# Low_jitter_CLK_bypass.net
KiCad netlist of a schematic drawn in Altium Designer
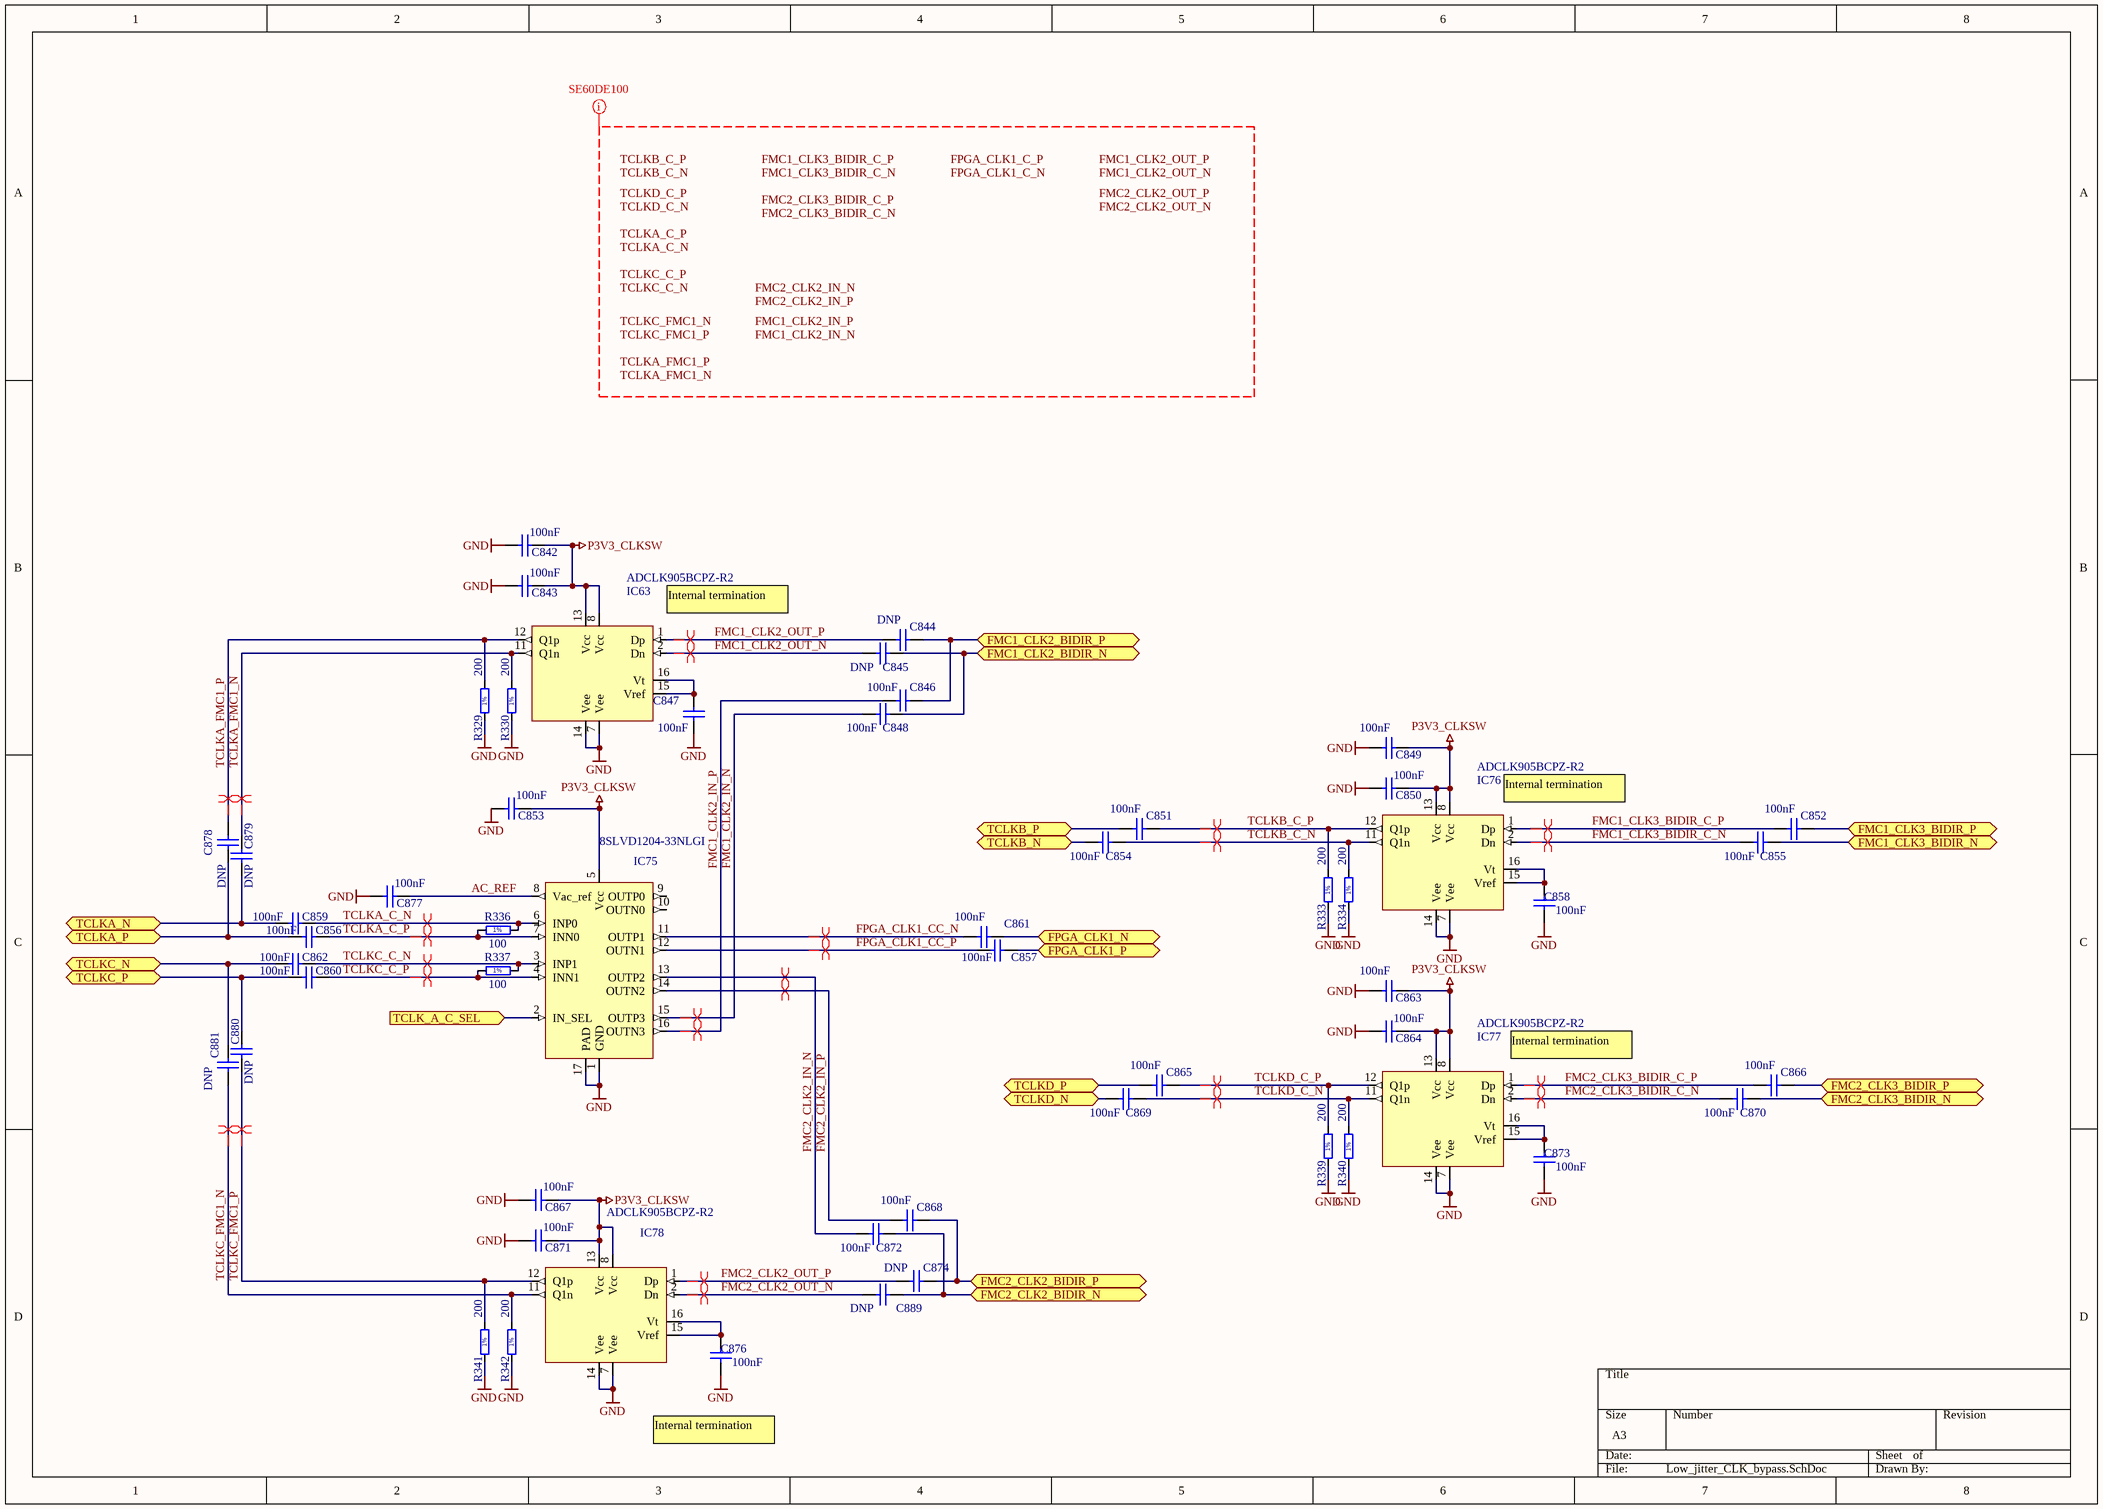
[diagram p0: Low_jitter_CLK_bypass.SchDoc]

(export (version "E")
  (design (tool "Eeschema 10.0.6"))
  (components
    (comp (ref "C842")
      (value "100nF")
      (footprint "CAPC0603X33N")
      (description "Non-polarised capacitor")
      (fields
        (field (name "PART NUMBER") "CC0201_100NF_6.3V_10%_X5R")
        (field (name "VOLTAGE") "6.3V")
        (field (name "AUTHOR") "CERN DEM JLC")
      )
      (libsource (lib "Capacitors") (part "Capacitor - non polarized"))
    )
    (comp (ref "C843")
      (value "100nF")
      (footprint "CAPC0603X33N")
      (description "Non-polarised capacitor")
      (fields
        (field (name "PART NUMBER") "CC0201_100NF_6.3V_10%_X5R")
        (field (name "VOLTAGE") "6.3V")
        (field (name "AUTHOR") "CERN DEM JLC")
      )
      (libsource (lib "Capacitors") (part "Capacitor - non polarized"))
    )
    (comp (ref "C844")
      (value "DNP")
      (footprint "CAPC0603X33N")
      (description "Non-polarised capacitor")
      (fields
        (field (name "PART NUMBER") "CC0201_100NF_6.3V_10%_X5R")
        (field (name "VOLTAGE") "6.3V")
        (field (name "AUTHOR") "CERN DEM JLC")
      )
      (libsource (lib "Capacitors") (part "Capacitor - non polarized"))
    )
    (comp (ref "C845")
      (value "DNP")
      (footprint "CAPC0603X33N")
      (description "Non-polarised capacitor")
      (fields
        (field (name "PART NUMBER") "CC0201_100NF_6.3V_10%_X5R")
        (field (name "VOLTAGE") "6.3V")
        (field (name "AUTHOR") "CERN DEM JLC")
      )
      (libsource (lib "Capacitors") (part "Capacitor - non polarized"))
    )
    (comp (ref "C846")
      (value "100nF")
      (footprint "CAPC0603X33N")
      (description "Non-polarised capacitor")
      (fields
        (field (name "PART NUMBER") "CC0201_100NF_6.3V_10%_X5R")
        (field (name "VOLTAGE") "6.3V")
        (field (name "AUTHOR") "CERN DEM JLC")
      )
      (libsource (lib "Capacitors") (part "Capacitor - non polarized"))
    )
    (comp (ref "C847")
      (value "100nF")
      (footprint "CAPC0603X33N")
      (description "Non-polarised capacitor")
      (fields
        (field (name "PART NUMBER") "CC0201_100NF_6.3V_10%_X5R")
        (field (name "VOLTAGE") "6.3V")
        (field (name "AUTHOR") "CERN DEM JLC")
      )
      (libsource (lib "Capacitors") (part "Capacitor - non polarized"))
    )
    (comp (ref "C848")
      (value "100nF")
      (footprint "CAPC0603X33N")
      (description "Non-polarised capacitor")
      (fields
        (field (name "PART NUMBER") "CC0201_100NF_6.3V_10%_X5R")
        (field (name "VOLTAGE") "6.3V")
        (field (name "AUTHOR") "CERN DEM JLC")
      )
      (libsource (lib "Capacitors") (part "Capacitor - non polarized"))
    )
    (comp (ref "C849")
      (value "100nF")
      (footprint "CAPC0603X33N")
      (description "Non-polarised capacitor")
      (fields
        (field (name "PART NUMBER") "CC0201_100NF_6.3V_10%_X5R")
        (field (name "VOLTAGE") "6.3V")
        (field (name "AUTHOR") "CERN DEM JLC")
      )
      (libsource (lib "Capacitors") (part "Capacitor - non polarized"))
    )
    (comp (ref "C850")
      (value "100nF")
      (footprint "CAPC0603X33N")
      (description "Non-polarised capacitor")
      (fields
        (field (name "PART NUMBER") "CC0201_100NF_6.3V_10%_X5R")
        (field (name "VOLTAGE") "6.3V")
        (field (name "AUTHOR") "CERN DEM JLC")
      )
      (libsource (lib "Capacitors") (part "Capacitor - non polarized"))
    )
    (comp (ref "C851")
      (value "100nF")
      (footprint "CAPC0603X33N")
      (description "Non-polarised capacitor")
      (fields
        (field (name "PART NUMBER") "CC0201_100NF_6.3V_10%_X5R")
        (field (name "VOLTAGE") "6.3V")
        (field (name "AUTHOR") "CERN DEM JLC")
      )
      (libsource (lib "Capacitors") (part "Capacitor - non polarized"))
    )
    (comp (ref "C852")
      (value "100nF")
      (footprint "CAPC0603X33N")
      (description "Non-polarised capacitor")
      (fields
        (field (name "PART NUMBER") "CC0201_100NF_6.3V_10%_X5R")
        (field (name "VOLTAGE") "6.3V")
        (field (name "AUTHOR") "CERN DEM JLC")
      )
      (libsource (lib "Capacitors") (part "Capacitor - non polarized"))
    )
    (comp (ref "C853")
      (value "100nF")
      (footprint "CAPC0603X33N")
      (description "Non-polarised capacitor")
      (fields
        (field (name "PART NUMBER") "CC0201_100NF_6.3V_10%_X5R")
        (field (name "VOLTAGE") "6.3V")
        (field (name "AUTHOR") "CERN DEM JLC")
      )
      (libsource (lib "Capacitors") (part "Capacitor - non polarized"))
    )
    (comp (ref "C854")
      (value "100nF")
      (footprint "CAPC0603X33N")
      (description "Non-polarised capacitor")
      (fields
        (field (name "PART NUMBER") "CC0201_100NF_6.3V_10%_X5R")
        (field (name "VOLTAGE") "6.3V")
        (field (name "AUTHOR") "CERN DEM JLC")
      )
      (libsource (lib "Capacitors") (part "Capacitor - non polarized"))
    )
    (comp (ref "C855")
      (value "100nF")
      (footprint "CAPC0603X33N")
      (description "Non-polarised capacitor")
      (fields
        (field (name "PART NUMBER") "CC0201_100NF_6.3V_10%_X5R")
        (field (name "VOLTAGE") "6.3V")
        (field (name "AUTHOR") "CERN DEM JLC")
      )
      (libsource (lib "Capacitors") (part "Capacitor - non polarized"))
    )
    (comp (ref "C856")
      (value "100nF")
      (footprint "CAPC0603X33N")
      (description "Non-polarised capacitor")
      (fields
        (field (name "PART NUMBER") "CC0201_100NF_6.3V_10%_X5R")
        (field (name "VOLTAGE") "6.3V")
        (field (name "AUTHOR") "CERN DEM JLC")
      )
      (libsource (lib "Capacitors") (part "Capacitor - non polarized"))
    )
    (comp (ref "C857")
      (value "100nF")
      (footprint "CAPC0603X33N")
      (description "Non-polarised capacitor")
      (fields
        (field (name "PART NUMBER") "CC0201_100NF_6.3V_10%_X5R")
        (field (name "VOLTAGE") "6.3V")
        (field (name "AUTHOR") "CERN DEM JLC")
      )
      (libsource (lib "Capacitors") (part "Capacitor - non polarized"))
    )
    (comp (ref "C858")
      (value "100nF")
      (footprint "CAPC0603X33N")
      (description "Non-polarised capacitor")
      (fields
        (field (name "PART NUMBER") "CC0201_100NF_6.3V_10%_X5R")
        (field (name "VOLTAGE") "6.3V")
        (field (name "AUTHOR") "CERN DEM JLC")
      )
      (libsource (lib "Capacitors") (part "Capacitor - non polarized"))
    )
    (comp (ref "C859")
      (value "100nF")
      (footprint "CAPC0603X33N")
      (description "Non-polarised capacitor")
      (fields
        (field (name "PART NUMBER") "CC0201_100NF_6.3V_10%_X5R")
        (field (name "VOLTAGE") "6.3V")
        (field (name "AUTHOR") "CERN DEM JLC")
      )
      (libsource (lib "Capacitors") (part "Capacitor - non polarized"))
    )
    (comp (ref "C860")
      (value "100nF")
      (footprint "CAPC0603X33N")
      (description "Non-polarised capacitor")
      (fields
        (field (name "PART NUMBER") "CC0201_100NF_6.3V_10%_X5R")
        (field (name "VOLTAGE") "6.3V")
        (field (name "AUTHOR") "CERN DEM JLC")
      )
      (libsource (lib "Capacitors") (part "Capacitor - non polarized"))
    )
    (comp (ref "C861")
      (value "100nF")
      (footprint "CAPC0603X33N")
      (description "Non-polarised capacitor")
      (fields
        (field (name "PART NUMBER") "CC0201_100NF_6.3V_10%_X5R")
        (field (name "VOLTAGE") "6.3V")
        (field (name "AUTHOR") "CERN DEM JLC")
      )
      (libsource (lib "Capacitors") (part "Capacitor - non polarized"))
    )
    (comp (ref "C862")
      (value "100nF")
      (footprint "CAPC0603X33N")
      (description "Non-polarised capacitor")
      (fields
        (field (name "PART NUMBER") "CC0201_100NF_6.3V_10%_X5R")
        (field (name "VOLTAGE") "6.3V")
        (field (name "AUTHOR") "CERN DEM JLC")
      )
      (libsource (lib "Capacitors") (part "Capacitor - non polarized"))
    )
    (comp (ref "C863")
      (value "100nF")
      (footprint "CAPC0603X33N")
      (description "Non-polarised capacitor")
      (fields
        (field (name "PART NUMBER") "CC0201_100NF_6.3V_10%_X5R")
        (field (name "VOLTAGE") "6.3V")
        (field (name "AUTHOR") "CERN DEM JLC")
      )
      (libsource (lib "Capacitors") (part "Capacitor - non polarized"))
    )
    (comp (ref "C864")
      (value "100nF")
      (footprint "CAPC0603X33N")
      (description "Non-polarised capacitor")
      (fields
        (field (name "PART NUMBER") "CC0201_100NF_6.3V_10%_X5R")
        (field (name "VOLTAGE") "6.3V")
        (field (name "AUTHOR") "CERN DEM JLC")
      )
      (libsource (lib "Capacitors") (part "Capacitor - non polarized"))
    )
    (comp (ref "C865")
      (value "100nF")
      (footprint "CAPC0603X33N")
      (description "Non-polarised capacitor")
      (fields
        (field (name "PART NUMBER") "CC0201_100NF_6.3V_10%_X5R")
        (field (name "VOLTAGE") "6.3V")
        (field (name "AUTHOR") "CERN DEM JLC")
      )
      (libsource (lib "Capacitors") (part "Capacitor - non polarized"))
    )
    (comp (ref "C866")
      (value "100nF")
      (footprint "CAPC0603X33N")
      (description "Non-polarised capacitor")
      (fields
        (field (name "PART NUMBER") "CC0201_100NF_6.3V_10%_X5R")
        (field (name "VOLTAGE") "6.3V")
        (field (name "AUTHOR") "CERN DEM JLC")
      )
      (libsource (lib "Capacitors") (part "Capacitor - non polarized"))
    )
    (comp (ref "C867")
      (value "100nF")
      (footprint "CAPC0603X33N")
      (description "Non-polarised capacitor")
      (fields
        (field (name "PART NUMBER") "CC0201_100NF_6.3V_10%_X5R")
        (field (name "VOLTAGE") "6.3V")
        (field (name "AUTHOR") "CERN DEM JLC")
      )
      (libsource (lib "Capacitors") (part "Capacitor - non polarized"))
    )
    (comp (ref "C868")
      (value "100nF")
      (footprint "CAPC0603X33N")
      (description "Non-polarised capacitor")
      (fields
        (field (name "PART NUMBER") "CC0201_100NF_6.3V_10%_X5R")
        (field (name "VOLTAGE") "6.3V")
        (field (name "AUTHOR") "CERN DEM JLC")
      )
      (libsource (lib "Capacitors") (part "Capacitor - non polarized"))
    )
    (comp (ref "C869")
      (value "100nF")
      (footprint "CAPC0603X33N")
      (description "Non-polarised capacitor")
      (fields
        (field (name "PART NUMBER") "CC0201_100NF_6.3V_10%_X5R")
        (field (name "VOLTAGE") "6.3V")
        (field (name "AUTHOR") "CERN DEM JLC")
      )
      (libsource (lib "Capacitors") (part "Capacitor - non polarized"))
    )
    (comp (ref "C870")
      (value "100nF")
      (footprint "CAPC0603X33N")
      (description "Non-polarised capacitor")
      (fields
        (field (name "PART NUMBER") "CC0201_100NF_6.3V_10%_X5R")
        (field (name "VOLTAGE") "6.3V")
        (field (name "AUTHOR") "CERN DEM JLC")
      )
      (libsource (lib "Capacitors") (part "Capacitor - non polarized"))
    )
    (comp (ref "C871")
      (value "100nF")
      (footprint "CAPC0603X33N")
      (description "Non-polarised capacitor")
      (fields
        (field (name "PART NUMBER") "CC0201_100NF_6.3V_10%_X5R")
        (field (name "VOLTAGE") "6.3V")
        (field (name "AUTHOR") "CERN DEM JLC")
      )
      (libsource (lib "Capacitors") (part "Capacitor - non polarized"))
    )
    (comp (ref "C872")
      (value "100nF")
      (footprint "CAPC0603X33N")
      (description "Non-polarised capacitor")
      (fields
        (field (name "PART NUMBER") "CC0201_100NF_6.3V_10%_X5R")
        (field (name "VOLTAGE") "6.3V")
        (field (name "AUTHOR") "CERN DEM JLC")
      )
      (libsource (lib "Capacitors") (part "Capacitor - non polarized"))
    )
    (comp (ref "C873")
      (value "100nF")
      (footprint "CAPC0603X33N")
      (description "Non-polarised capacitor")
      (fields
        (field (name "PART NUMBER") "CC0201_100NF_6.3V_10%_X5R")
        (field (name "VOLTAGE") "6.3V")
        (field (name "AUTHOR") "CERN DEM JLC")
      )
      (libsource (lib "Capacitors") (part "Capacitor - non polarized"))
    )
    (comp (ref "C874")
      (value "DNP")
      (footprint "CAPC0603X33N")
      (description "Non-polarised capacitor")
      (fields
        (field (name "PART NUMBER") "CC0201_100NF_6.3V_10%_X5R")
        (field (name "VOLTAGE") "6.3V")
        (field (name "AUTHOR") "CERN DEM JLC")
      )
      (libsource (lib "Capacitors") (part "Capacitor - non polarized"))
    )
    (comp (ref "C876")
      (value "100nF")
      (footprint "CAPC0603X33N")
      (description "Non-polarised capacitor")
      (fields
        (field (name "PART NUMBER") "CC0201_100NF_6.3V_10%_X5R")
        (field (name "VOLTAGE") "6.3V")
        (field (name "AUTHOR") "CERN DEM JLC")
      )
      (libsource (lib "Capacitors") (part "Capacitor - non polarized"))
    )
    (comp (ref "C877")
      (value "100nF")
      (footprint "CAPC0603X33N")
      (description "Non-polarised capacitor")
      (fields
        (field (name "PART NUMBER") "CC0201_100NF_6.3V_10%_X5R")
        (field (name "VOLTAGE") "6.3V")
        (field (name "AUTHOR") "CERN DEM JLC")
      )
      (libsource (lib "Capacitors") (part "Capacitor - non polarized"))
    )
    (comp (ref "C878")
      (value "DNP")
      (footprint "CAPC0603X33N")
      (description "Non-polarised capacitor")
      (fields
        (field (name "PART NUMBER") "CC0201_100NF_6.3V_10%_X5R")
        (field (name "VOLTAGE") "6.3V")
        (field (name "AUTHOR") "CERN DEM JLC")
      )
      (libsource (lib "Capacitors") (part "Capacitor - non polarized"))
    )
    (comp (ref "C879")
      (value "DNP")
      (footprint "CAPC0603X33N")
      (description "Non-polarised capacitor")
      (fields
        (field (name "PART NUMBER") "CC0201_100NF_6.3V_10%_X5R")
        (field (name "VOLTAGE") "6.3V")
        (field (name "AUTHOR") "CERN DEM JLC")
      )
      (libsource (lib "Capacitors") (part "Capacitor - non polarized"))
    )
    (comp (ref "C880")
      (value "DNP")
      (footprint "CAPC0603X33N")
      (description "Non-polarised capacitor")
      (fields
        (field (name "PART NUMBER") "CC0201_100NF_6.3V_10%_X5R")
        (field (name "VOLTAGE") "6.3V")
        (field (name "AUTHOR") "CERN DEM JLC")
      )
      (libsource (lib "Capacitors") (part "Capacitor - non polarized"))
    )
    (comp (ref "C881")
      (value "DNP")
      (footprint "CAPC0603X33N")
      (description "Non-polarised capacitor")
      (fields
        (field (name "PART NUMBER") "CC0201_100NF_6.3V_10%_X5R")
        (field (name "VOLTAGE") "6.3V")
        (field (name "AUTHOR") "CERN DEM JLC")
      )
      (libsource (lib "Capacitors") (part "Capacitor - non polarized"))
    )
    (comp (ref "C889")
      (value "DNP")
      (footprint "CAPC0603X33N")
      (description "Non-polarised capacitor")
      (fields
        (field (name "PART NUMBER") "CC0201_100NF_6.3V_10%_X5R")
        (field (name "VOLTAGE") "6.3V")
        (field (name "AUTHOR") "CERN DEM JLC")
      )
      (libsource (lib "Capacitors") (part "Capacitor - non polarized"))
    )
    (comp (ref "IC63")
      (value "ADCLK905BCPZ-R2")
      (footprint "CP-16-3")
      (description "clock distributor")
      (libsource (lib "LIBRARY_SCH") (part "CLOCK_ADCLK905"))
    )
    (comp (ref "IC75")
      (value "8SLVD1204-33NLGI")
      (footprint "QFN50P300X300X100-16N")
      (description "2:4, LVDS Output Fanout Buffer, 3.3V")
      (libsource (lib "LIBRARY_SCH") (part "CLOCK_IDT8SLVD1204-33"))
    )
    (comp (ref "IC76")
      (value "ADCLK905BCPZ-R2")
      (footprint "CP-16-3")
      (description "clock distributor")
      (libsource (lib "LIBRARY_SCH") (part "CLOCK_ADCLK905"))
    )
    (comp (ref "IC77")
      (value "ADCLK905BCPZ-R2")
      (footprint "CP-16-3")
      (description "clock distributor")
      (libsource (lib "LIBRARY_SCH") (part "CLOCK_ADCLK905"))
    )
    (comp (ref "IC78")
      (value "ADCLK905BCPZ-R2")
      (footprint "CP-16-3")
      (description "clock distributor")
      (libsource (lib "LIBRARY_SCH") (part "CLOCK_ADCLK905"))
    )
    (comp (ref "R329")
      (value "200")
      (footprint "RESC1005X40N")
      (description "Resistor - 1%")
      (fields
        (field (name "PART NUMBER") "R0402_200R_1%_0.0625W_100PPM")
        (field (name "POWER") "0.0625W")
        (field (name "AUTHOR") "CERN DEM JLC")
      )
      (libsource (lib "Resistors") (part "Resistor - 1%"))
    )
    (comp (ref "R330")
      (value "200")
      (footprint "RESC1005X40N")
      (description "Resistor - 1%")
      (fields
        (field (name "PART NUMBER") "R0402_200R_1%_0.0625W_100PPM")
        (field (name "POWER") "0.0625W")
        (field (name "AUTHOR") "CERN DEM JLC")
      )
      (libsource (lib "Resistors") (part "Resistor - 1%"))
    )
    (comp (ref "R333")
      (value "200")
      (footprint "RESC1005X40N")
      (description "Resistor - 1%")
      (fields
        (field (name "PART NUMBER") "R0402_200R_1%_0.0625W_100PPM")
        (field (name "POWER") "0.0625W")
        (field (name "AUTHOR") "CERN DEM JLC")
      )
      (libsource (lib "Resistors") (part "Resistor - 1%"))
    )
    (comp (ref "R334")
      (value "200")
      (footprint "RESC1005X40N")
      (description "Resistor - 1%")
      (fields
        (field (name "PART NUMBER") "R0402_200R_1%_0.0625W_100PPM")
        (field (name "POWER") "0.0625W")
        (field (name "AUTHOR") "CERN DEM JLC")
      )
      (libsource (lib "Resistors") (part "Resistor - 1%"))
    )
    (comp (ref "R336")
      (value "100")
      (footprint "RESC1005X40N")
      (description "Resistor - 1%")
      (fields
        (field (name "PART NUMBER") "R0402_100R_1%_0.0625W_100PPM")
        (field (name "POWER") "0.0625W")
        (field (name "AUTHOR") "CERN DEM JLC")
      )
      (libsource (lib "Resistors") (part "Resistor - 1%"))
    )
    (comp (ref "R337")
      (value "100")
      (footprint "RESC1005X40N")
      (description "Resistor - 1%")
      (fields
        (field (name "PART NUMBER") "R0402_100R_1%_0.0625W_100PPM")
        (field (name "POWER") "0.0625W")
        (field (name "AUTHOR") "CERN DEM JLC")
      )
      (libsource (lib "Resistors") (part "Resistor - 1%"))
    )
    (comp (ref "R339")
      (value "200")
      (footprint "RESC1005X40N")
      (description "Resistor - 1%")
      (fields
        (field (name "PART NUMBER") "R0402_200R_1%_0.0625W_100PPM")
        (field (name "POWER") "0.0625W")
        (field (name "AUTHOR") "CERN DEM JLC")
      )
      (libsource (lib "Resistors") (part "Resistor - 1%"))
    )
    (comp (ref "R340")
      (value "200")
      (footprint "RESC1005X40N")
      (description "Resistor - 1%")
      (fields
        (field (name "PART NUMBER") "R0402_200R_1%_0.0625W_100PPM")
        (field (name "POWER") "0.0625W")
        (field (name "AUTHOR") "CERN DEM JLC")
      )
      (libsource (lib "Resistors") (part "Resistor - 1%"))
    )
    (comp (ref "R341")
      (value "200")
      (footprint "RESC1005X40N")
      (description "Resistor - 1%")
      (fields
        (field (name "PART NUMBER") "R0402_200R_1%_0.0625W_100PPM")
        (field (name "POWER") "0.0625W")
        (field (name "AUTHOR") "CERN DEM JLC")
      )
      (libsource (lib "Resistors") (part "Resistor - 1%"))
    )
    (comp (ref "R342")
      (value "200")
      (footprint "RESC1005X40N")
      (description "Resistor - 1%")
      (fields
        (field (name "PART NUMBER") "R0402_200R_1%_0.0625W_100PPM")
        (field (name "POWER") "0.0625W")
        (field (name "AUTHOR") "CERN DEM JLC")
      )
      (libsource (lib "Resistors") (part "Resistor - 1%"))
    )
  )
  (nets
    (net (code "1") (name "/AC_REF") (class "Default")
      (node (ref "C877") (pin "2") (pinfunction "2_2") (pintype "passive"))
      (node (ref "IC75") (pin "8") (pinfunction "Vac_ref_8") (pintype "output"))
    )
    (net (code "2") (name "/FMC1_CLK2_BIDIR_N") (class "Default")
      (node (ref "C845") (pin "2") (pinfunction "2_2") (pintype "passive"))
      (node (ref "C848") (pin "2") (pinfunction "2_2") (pintype "passive"))
    )
    (net (code "3") (name "/FMC1_CLK2_BIDIR_P") (class "Default")
      (node (ref "C844") (pin "2") (pinfunction "2_2") (pintype "passive"))
      (node (ref "C846") (pin "2") (pinfunction "2_2") (pintype "passive"))
    )
    (net (code "4") (name "/FMC1_CLK2_IN_N") (class "Default")
      (node (ref "C848") (pin "1") (pinfunction "1_1") (pintype "passive"))
      (node (ref "IC75") (pin "15") (pinfunction "OUTP3_15") (pintype "output"))
    )
    (net (code "5") (name "/FMC1_CLK2_IN_P") (class "Default")
      (node (ref "C846") (pin "1") (pinfunction "1_1") (pintype "passive"))
      (node (ref "IC75") (pin "16") (pinfunction "OUTN3_16") (pintype "output"))
    )
    (net (code "6") (name "/FMC1_CLK2_OUT_N") (class "Default")
      (node (ref "C845") (pin "1") (pinfunction "1_1") (pintype "passive"))
      (node (ref "IC63") (pin "2") (pinfunction "Dn_2") (pintype "input"))
    )
    (net (code "7") (name "/FMC1_CLK2_OUT_P") (class "Default")
      (node (ref "C844") (pin "1") (pinfunction "1_1") (pintype "passive"))
      (node (ref "IC63") (pin "1") (pinfunction "Dp_1") (pintype "input"))
    )
    (net (code "8") (name "/FMC1_CLK3_BIDIR_C_N") (class "Default")
      (node (ref "C855") (pin "1") (pinfunction "1_1") (pintype "passive"))
      (node (ref "IC76") (pin "2") (pinfunction "Dn_2") (pintype "input"))
    )
    (net (code "9") (name "/FMC1_CLK3_BIDIR_C_P") (class "Default")
      (node (ref "C852") (pin "1") (pinfunction "1_1") (pintype "passive"))
      (node (ref "IC76") (pin "1") (pinfunction "Dp_1") (pintype "input"))
    )
    (net (code "10") (name "/FMC1_CLK3_BIDIR_N") (class "Default")
      (node (ref "C855") (pin "2") (pinfunction "2_2") (pintype "passive"))
    )
    (net (code "11") (name "/FMC1_CLK3_BIDIR_P") (class "Default")
      (node (ref "C852") (pin "2") (pinfunction "2_2") (pintype "passive"))
    )
    (net (code "12") (name "/FMC2_CLK2_BIDIR_N") (class "Default")
      (node (ref "C872") (pin "2") (pinfunction "2_2") (pintype "passive"))
      (node (ref "C889") (pin "2") (pinfunction "2_2") (pintype "passive"))
    )
    (net (code "13") (name "/FMC2_CLK2_BIDIR_P") (class "Default")
      (node (ref "C868") (pin "2") (pinfunction "2_2") (pintype "passive"))
      (node (ref "C874") (pin "2") (pinfunction "2_2") (pintype "passive"))
    )
    (net (code "14") (name "/FMC2_CLK2_IN_N") (class "Default")
      (node (ref "C872") (pin "1") (pinfunction "1_1") (pintype "passive"))
      (node (ref "IC75") (pin "13") (pinfunction "OUTP2_13") (pintype "output"))
    )
    (net (code "15") (name "/FMC2_CLK2_IN_P") (class "Default")
      (node (ref "C868") (pin "1") (pinfunction "1_1") (pintype "passive"))
      (node (ref "IC75") (pin "14") (pinfunction "OUTN2_14") (pintype "output"))
    )
    (net (code "16") (name "/FMC2_CLK2_OUT_N") (class "Default")
      (node (ref "C889") (pin "1") (pinfunction "1_1") (pintype "passive"))
      (node (ref "IC78") (pin "2") (pinfunction "Dn_2") (pintype "input"))
    )
    (net (code "17") (name "/FMC2_CLK2_OUT_P") (class "Default")
      (node (ref "C874") (pin "1") (pinfunction "1_1") (pintype "passive"))
      (node (ref "IC78") (pin "1") (pinfunction "Dp_1") (pintype "input"))
    )
    (net (code "18") (name "/FMC2_CLK3_BIDIR_C_N") (class "Default")
      (node (ref "C870") (pin "1") (pinfunction "1_1") (pintype "passive"))
      (node (ref "IC77") (pin "2") (pinfunction "Dn_2") (pintype "input"))
    )
    (net (code "19") (name "/FMC2_CLK3_BIDIR_C_P") (class "Default")
      (node (ref "C866") (pin "1") (pinfunction "1_1") (pintype "passive"))
      (node (ref "IC77") (pin "1") (pinfunction "Dp_1") (pintype "input"))
    )
    (net (code "20") (name "/FMC2_CLK3_BIDIR_N") (class "Default")
      (node (ref "C870") (pin "2") (pinfunction "2_2") (pintype "passive"))
    )
    (net (code "21") (name "/FMC2_CLK3_BIDIR_P") (class "Default")
      (node (ref "C866") (pin "2") (pinfunction "2_2") (pintype "passive"))
    )
    (net (code "22") (name "/FPGA_CLK1_CC_N") (class "Default")
      (node (ref "C861") (pin "1") (pinfunction "1_1") (pintype "passive"))
      (node (ref "IC75") (pin "11") (pinfunction "OUTP1_11") (pintype "output"))
    )
    (net (code "23") (name "/FPGA_CLK1_CC_P") (class "Default")
      (node (ref "C857") (pin "1") (pinfunction "1_1") (pintype "passive"))
      (node (ref "IC75") (pin "12") (pinfunction "OUTN1_12") (pintype "output"))
    )
    (net (code "26") (name "/FPGA_CLK1_N") (class "Default")
      (node (ref "C861") (pin "2") (pinfunction "2_2") (pintype "passive"))
    )
    (net (code "27") (name "/FPGA_CLK1_P") (class "Default")
      (node (ref "C857") (pin "2") (pinfunction "2_2") (pintype "passive"))
    )
    (net (code "28") (name "/TCLKA_C_N") (class "Default")
      (node (ref "C859") (pin "2") (pinfunction "2_2") (pintype "passive"))
      (node (ref "IC75") (pin "6") (pinfunction "INP0_6") (pintype "input"))
      (node (ref "R336") (pin "2") (pinfunction "2_2") (pintype "passive"))
    )
    (net (code "29") (name "/TCLKA_C_P") (class "Default")
      (node (ref "C856") (pin "2") (pinfunction "2_2") (pintype "passive"))
      (node (ref "IC75") (pin "7") (pinfunction "INN0_7") (pintype "input"))
      (node (ref "R336") (pin "1") (pinfunction "1_1") (pintype "passive"))
    )
    (net (code "30") (name "/TCLKA_FMC1_N") (class "Default")
      (node (ref "C879") (pin "2") (pinfunction "2_2") (pintype "passive"))
      (node (ref "IC63") (pin "11") (pinfunction "Q1n_11") (pintype "output"))
      (node (ref "R330") (pin "2") (pinfunction "2_2") (pintype "passive"))
    )
    (net (code "31") (name "/TCLKA_FMC1_P") (class "Default")
      (node (ref "C878") (pin "2") (pinfunction "2_2") (pintype "passive"))
      (node (ref "IC63") (pin "12") (pinfunction "Q1p_12") (pintype "output"))
      (node (ref "R329") (pin "2") (pinfunction "2_2") (pintype "passive"))
    )
    (net (code "32") (name "/TCLKA_N") (class "Default")
      (node (ref "C859") (pin "1") (pinfunction "1_1") (pintype "passive"))
      (node (ref "C879") (pin "1") (pinfunction "1_1") (pintype "passive"))
    )
    (net (code "33") (name "/TCLKA_P") (class "Default")
      (node (ref "C856") (pin "1") (pinfunction "1_1") (pintype "passive"))
      (node (ref "C878") (pin "1") (pinfunction "1_1") (pintype "passive"))
    )
    (net (code "34") (name "/TCLKB_C_N") (class "Default")
      (node (ref "C854") (pin "2") (pinfunction "2_2") (pintype "passive"))
      (node (ref "IC76") (pin "11") (pinfunction "Q1n_11") (pintype "output"))
      (node (ref "R334") (pin "2") (pinfunction "2_2") (pintype "passive"))
    )
    (net (code "35") (name "/TCLKB_C_P") (class "Default")
      (node (ref "C851") (pin "2") (pinfunction "2_2") (pintype "passive"))
      (node (ref "IC76") (pin "12") (pinfunction "Q1p_12") (pintype "output"))
      (node (ref "R333") (pin "2") (pinfunction "2_2") (pintype "passive"))
    )
    (net (code "36") (name "/TCLKB_N") (class "Default")
      (node (ref "C854") (pin "1") (pinfunction "1_1") (pintype "passive"))
    )
    (net (code "37") (name "/TCLKB_P") (class "Default")
      (node (ref "C851") (pin "1") (pinfunction "1_1") (pintype "passive"))
    )
    (net (code "38") (name "/TCLKC_C_N") (class "Default")
      (node (ref "C862") (pin "2") (pinfunction "2_2") (pintype "passive"))
      (node (ref "IC75") (pin "3") (pinfunction "INP1_3") (pintype "input"))
      (node (ref "R337") (pin "2") (pinfunction "2_2") (pintype "passive"))
    )
    (net (code "39") (name "/TCLKC_C_P") (class "Default")
      (node (ref "C860") (pin "2") (pinfunction "2_2") (pintype "passive"))
      (node (ref "IC75") (pin "4") (pinfunction "INN1_4") (pintype "input"))
      (node (ref "R337") (pin "1") (pinfunction "1_1") (pintype "passive"))
    )
    (net (code "40") (name "/TCLKC_FMC1_N") (class "Default")
      (node (ref "C881") (pin "1") (pinfunction "1_1") (pintype "passive"))
      (node (ref "IC78") (pin "11") (pinfunction "Q1n_11") (pintype "output"))
      (node (ref "R342") (pin "2") (pinfunction "2_2") (pintype "passive"))
    )
    (net (code "41") (name "/TCLKC_FMC1_P") (class "Default")
      (node (ref "C880") (pin "1") (pinfunction "1_1") (pintype "passive"))
      (node (ref "IC78") (pin "12") (pinfunction "Q1p_12") (pintype "output"))
      (node (ref "R341") (pin "2") (pinfunction "2_2") (pintype "passive"))
    )
    (net (code "42") (name "/TCLKC_N") (class "Default")
      (node (ref "C862") (pin "1") (pinfunction "1_1") (pintype "passive"))
      (node (ref "C881") (pin "2") (pinfunction "2_2") (pintype "passive"))
    )
    (net (code "43") (name "/TCLKC_P") (class "Default")
      (node (ref "C860") (pin "1") (pinfunction "1_1") (pintype "passive"))
      (node (ref "C880") (pin "2") (pinfunction "2_2") (pintype "passive"))
    )
    (net (code "44") (name "/TCLKD_C_N") (class "Default")
      (node (ref "C869") (pin "2") (pinfunction "2_2") (pintype "passive"))
      (node (ref "IC77") (pin "11") (pinfunction "Q1n_11") (pintype "output"))
      (node (ref "R340") (pin "2") (pinfunction "2_2") (pintype "passive"))
    )
    (net (code "45") (name "/TCLKD_C_P") (class "Default")
      (node (ref "C865") (pin "2") (pinfunction "2_2") (pintype "passive"))
      (node (ref "IC77") (pin "12") (pinfunction "Q1p_12") (pintype "output"))
      (node (ref "R339") (pin "2") (pinfunction "2_2") (pintype "passive"))
    )
    (net (code "46") (name "/TCLKD_N") (class "Default")
      (node (ref "C869") (pin "1") (pinfunction "1_1") (pintype "passive"))
    )
    (net (code "47") (name "/TCLKD_P") (class "Default")
      (node (ref "C865") (pin "1") (pinfunction "1_1") (pintype "passive"))
    )
    (net (code "48") (name "/TCLK_A_C_SEL") (class "Default")
      (node (ref "IC75") (pin "2") (pinfunction "IN_SEL_2") (pintype "input"))
    )
    (net (code "49") (name "GND") (class "Default")
      (node (ref "C842") (pin "1") (pinfunction "1_1") (pintype "passive"))
      (node (ref "C843") (pin "1") (pinfunction "1_1") (pintype "passive"))
      (node (ref "C847") (pin "1") (pinfunction "1_1") (pintype "passive"))
      (node (ref "C849") (pin "1") (pinfunction "1_1") (pintype "passive"))
      (node (ref "C850") (pin "1") (pinfunction "1_1") (pintype "passive"))
      (node (ref "C853") (pin "1") (pinfunction "1_1") (pintype "passive"))
      (node (ref "C858") (pin "1") (pinfunction "1_1") (pintype "passive"))
      (node (ref "C863") (pin "1") (pinfunction "1_1") (pintype "passive"))
      (node (ref "C864") (pin "1") (pinfunction "1_1") (pintype "passive"))
      (node (ref "C867") (pin "1") (pinfunction "1_1") (pintype "passive"))
      (node (ref "C871") (pin "1") (pinfunction "1_1") (pintype "passive"))
      (node (ref "C873") (pin "1") (pinfunction "1_1") (pintype "passive"))
      (node (ref "C876") (pin "1") (pinfunction "1_1") (pintype "passive"))
      (node (ref "C877") (pin "1") (pinfunction "1_1") (pintype "passive"))
      (node (ref "IC63") (pin "14") (pinfunction "Vee_14") (pintype "power_in"))
      (node (ref "IC63") (pin "7") (pinfunction "Vee_7") (pintype "power_in"))
      (node (ref "IC75") (pin "1") (pinfunction "GND_1") (pintype "power_in"))
      (node (ref "IC75") (pin "17") (pinfunction "PAD_17") (pintype "power_in"))
      (node (ref "IC76") (pin "14") (pinfunction "Vee_14") (pintype "power_in"))
      (node (ref "IC76") (pin "7") (pinfunction "Vee_7") (pintype "power_in"))
      (node (ref "IC77") (pin "14") (pinfunction "Vee_14") (pintype "power_in"))
      (node (ref "IC77") (pin "7") (pinfunction "Vee_7") (pintype "power_in"))
      (node (ref "IC78") (pin "14") (pinfunction "Vee_14") (pintype "power_in"))
      (node (ref "IC78") (pin "7") (pinfunction "Vee_7") (pintype "power_in"))
      (node (ref "R329") (pin "1") (pinfunction "1_1") (pintype "passive"))
      (node (ref "R330") (pin "1") (pinfunction "1_1") (pintype "passive"))
      (node (ref "R333") (pin "1") (pinfunction "1_1") (pintype "passive"))
      (node (ref "R334") (pin "1") (pinfunction "1_1") (pintype "passive"))
      (node (ref "R339") (pin "1") (pinfunction "1_1") (pintype "passive"))
      (node (ref "R340") (pin "1") (pinfunction "1_1") (pintype "passive"))
      (node (ref "R341") (pin "1") (pinfunction "1_1") (pintype "passive"))
      (node (ref "R342") (pin "1") (pinfunction "1_1") (pintype "passive"))
    )
    (net (code "50") (name "Net-(IC63-Vref)") (class "Default")
      (node (ref "C847") (pin "2") (pinfunction "2_2") (pintype "passive"))
      (node (ref "IC63") (pin "15") (pinfunction "Vref_15") (pintype "power_in"))
      (node (ref "IC63") (pin "16") (pinfunction "Vt_16") (pintype "passive"))
    )
    (net (code "51") (name "Net-(IC76-Vref)") (class "Default")
      (node (ref "C858") (pin "2") (pinfunction "2_2") (pintype "passive"))
      (node (ref "IC76") (pin "15") (pinfunction "Vref_15") (pintype "power_in"))
      (node (ref "IC76") (pin "16") (pinfunction "Vt_16") (pintype "passive"))
    )
    (net (code "52") (name "Net-(IC77-Vref)") (class "Default")
      (node (ref "C873") (pin "2") (pinfunction "2_2") (pintype "passive"))
      (node (ref "IC77") (pin "15") (pinfunction "Vref_15") (pintype "power_in"))
      (node (ref "IC77") (pin "16") (pinfunction "Vt_16") (pintype "passive"))
    )
    (net (code "53") (name "Net-(IC78-Vref)") (class "Default")
      (node (ref "C876") (pin "2") (pinfunction "2_2") (pintype "passive"))
      (node (ref "IC78") (pin "15") (pinfunction "Vref_15") (pintype "power_in"))
      (node (ref "IC78") (pin "16") (pinfunction "Vt_16") (pintype "passive"))
    )
    (net (code "54") (name "P3V3_CLKSW") (class "Default")
      (node (ref "C842") (pin "2") (pinfunction "2_2") (pintype "passive"))
      (node (ref "C843") (pin "2") (pinfunction "2_2") (pintype "passive"))
      (node (ref "C849") (pin "2") (pinfunction "2_2") (pintype "passive"))
      (node (ref "C850") (pin "2") (pinfunction "2_2") (pintype "passive"))
      (node (ref "C853") (pin "2") (pinfunction "2_2") (pintype "passive"))
      (node (ref "C863") (pin "2") (pinfunction "2_2") (pintype "passive"))
      (node (ref "C864") (pin "2") (pinfunction "2_2") (pintype "passive"))
      (node (ref "C867") (pin "2") (pinfunction "2_2") (pintype "passive"))
      (node (ref "C871") (pin "2") (pinfunction "2_2") (pintype "passive"))
      (node (ref "IC63") (pin "13") (pinfunction "Vcc_13") (pintype "power_in"))
      (node (ref "IC63") (pin "8") (pinfunction "Vcc_8") (pintype "power_in"))
      (node (ref "IC75") (pin "5") (pinfunction "Vcc_5") (pintype "power_in"))
      (node (ref "IC76") (pin "13") (pinfunction "Vcc_13") (pintype "power_in"))
      (node (ref "IC76") (pin "8") (pinfunction "Vcc_8") (pintype "power_in"))
      (node (ref "IC77") (pin "13") (pinfunction "Vcc_13") (pintype "power_in"))
      (node (ref "IC77") (pin "8") (pinfunction "Vcc_8") (pintype "power_in"))
      (node (ref "IC78") (pin "13") (pinfunction "Vcc_13") (pintype "power_in"))
      (node (ref "IC78") (pin "8") (pinfunction "Vcc_8") (pintype "power_in"))
    )
    (net (code "55") (name "unconnected-(IC75-OUTN0-Pad10)") (class "Default")
      (node (ref "IC75") (pin "10") (pinfunction "OUTN0_10") (pintype "output"))
    )
    (net (code "56") (name "unconnected-(IC75-OUTP0-Pad9)") (class "Default")
      (node (ref "IC75") (pin "9") (pinfunction "OUTP0_9") (pintype "output"))
    )
  )
)
